# MG2639_Cellular_Shield.net
KiCad netlist of a schematic drawn in EAGLE
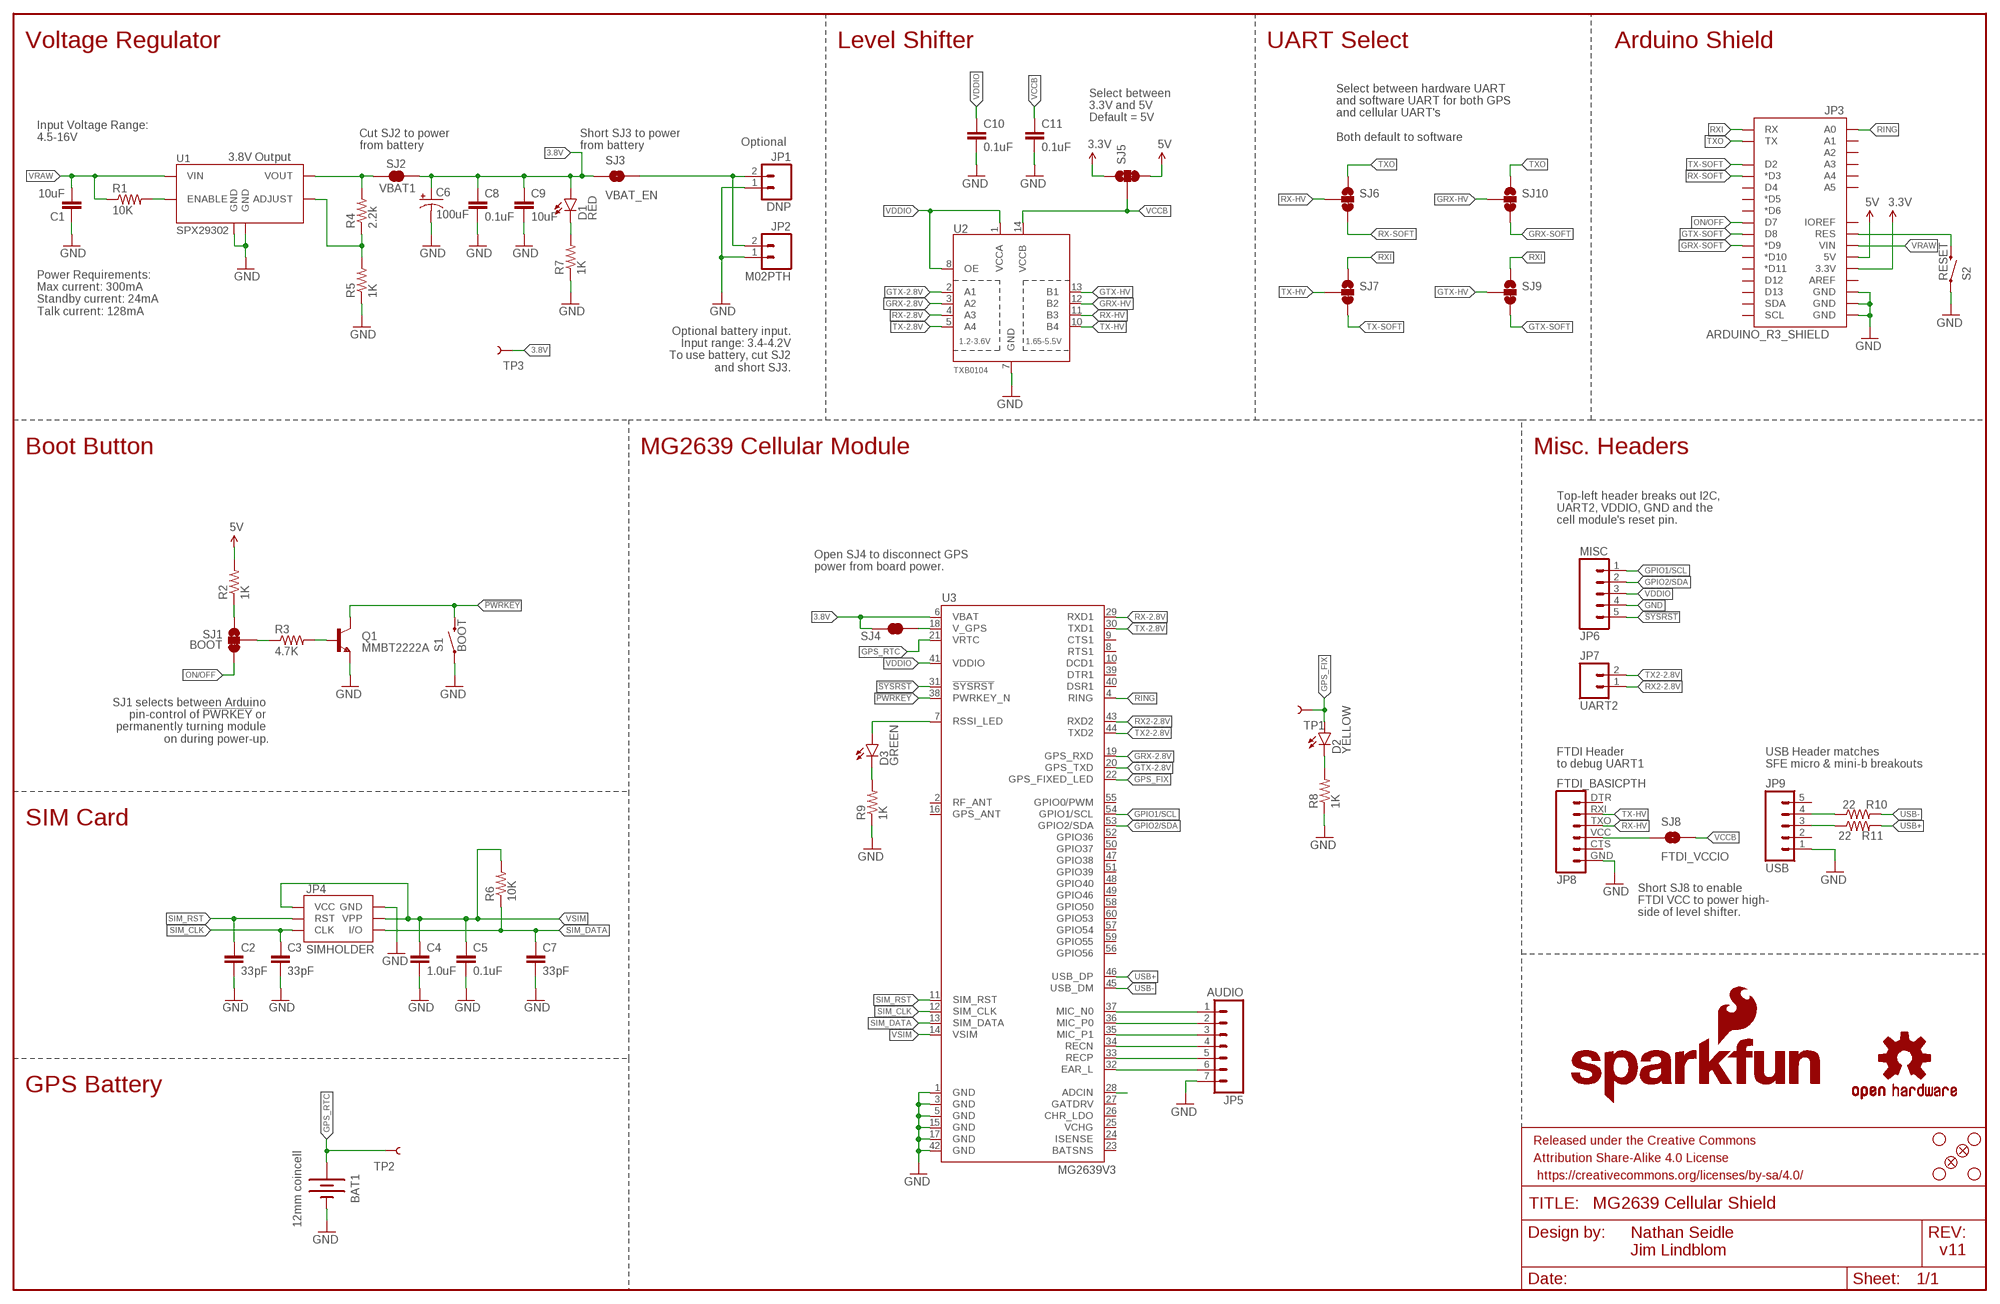
[diagram p0: schematic, sheet 1]

(export (version "E")
  (design (tool "Eeschema 10.0.6"))
  (components
    (comp (ref "BAT1")
      (value "12mm coincell")
      (footprint "eagle-import:BATTCON_12MM")
      (libsource (lib "eagle-import") (part "BATTERY12MM"))
    )
    (comp (ref "C1")
      (value "10uF")
      (footprint "eagle-import:1210")
      (libsource (lib "eagle-import") (part "10UF50V20%(1210)"))
    )
    (comp (ref "C2")
      (value "33pF")
      (footprint "eagle-import:0603-CAP")
      (libsource (lib "eagle-import") (part "33PF-50V-5%-(0603)"))
    )
    (comp (ref "C3")
      (value "33pF")
      (footprint "eagle-import:0603-CAP")
      (libsource (lib "eagle-import") (part "33PF-50V-5%-(0603)"))
    )
    (comp (ref "C4")
      (value "1.0uF")
      (footprint "eagle-import:0603-CAP")
      (libsource (lib "eagle-import") (part "1.0UF-16V-10%(0603)"))
    )
    (comp (ref "C5")
      (value "0.1uF")
      (footprint "eagle-import:0603-CAP")
      (libsource (lib "eagle-import") (part "0.1UF-25V(+80/-20%)(0603)"))
    )
    (comp (ref "C6")
      (value "100uF")
      (footprint "eagle-import:EIA7343")
      (libsource (lib "eagle-import") (part "100UF-10V-10%(TANT)"))
    )
    (comp (ref "C7")
      (value "33pF")
      (footprint "eagle-import:0603-CAP")
      (libsource (lib "eagle-import") (part "33PF-50V-5%-(0603)"))
    )
    (comp (ref "C8")
      (value "0.1uF")
      (footprint "eagle-import:0603-CAP")
      (libsource (lib "eagle-import") (part "0.1UF-25V(+80/-20%)(0603)"))
    )
    (comp (ref "C9")
      (value "10uF")
      (footprint "eagle-import:1210")
      (libsource (lib "eagle-import") (part "10UF50V20%(1210)"))
    )
    (comp (ref "C10")
      (value "0.1uF")
      (footprint "eagle-import:0603-CAP")
      (libsource (lib "eagle-import") (part "0.1UF-25V(+80/-20%)(0603)"))
    )
    (comp (ref "C11")
      (value "0.1uF")
      (footprint "eagle-import:0603-CAP")
      (libsource (lib "eagle-import") (part "0.1UF-25V(+80/-20%)(0603)"))
    )
    (comp (ref "D1")
      (value "RED")
      (footprint "eagle-import:LED-1206")
      (libsource (lib "eagle-import") (part "LED-RED1206"))
    )
    (comp (ref "D2")
      (value "YELLOW")
      (footprint "eagle-import:LED-1206")
      (libsource (lib "eagle-import") (part "LED-YELLOWLARGE"))
    )
    (comp (ref "D3")
      (value "GREEN")
      (footprint "eagle-import:LED-1206")
      (libsource (lib "eagle-import") (part "LED-GREENLARGE"))
    )
    (comp (ref "FID1")
      (value "FIDUCIAL1X2")
      (footprint "eagle-import:FIDUCIAL-1X2")
      (libsource (lib "eagle-import") (part "FIDUCIAL1X2"))
    )
    (comp (ref "FID2")
      (value "FIDUCIAL1X2")
      (footprint "eagle-import:FIDUCIAL-1X2")
      (libsource (lib "eagle-import") (part "FIDUCIAL1X2"))
    )
    (comp (ref "FRAME1")
      (value "FRAME-LEDGER")
      (footprint "eagle-import:CREATIVE_COMMONS")
      (libsource (lib "eagle-import") (part "FRAME-LEDGER"))
    )
    (comp (ref "JP1")
      (value "DNP")
      (footprint "eagle-import:JST-2-PTH")
      (libsource (lib "eagle-import") (part "M02JST-PTH-2"))
    )
    (comp (ref "JP2")
      (value "M02PTH")
      (footprint "eagle-import:1X02")
      (libsource (lib "eagle-import") (part "M02PTH"))
    )
    (comp (ref "JP3")
      (value "ARDUINO_R3_SHIELD")
      (footprint "eagle-import:UNO_R3_SHIELD_NOLABELS")
      (libsource (lib "eagle-import") (part "ARDUINO_R3_SHIELDNOLABELS"))
    )
    (comp (ref "JP4")
      (value "SIMHOLDER")
      (footprint "eagle-import:SIMHOLDER")
      (libsource (lib "eagle-import") (part "SIMHOLDERSIM"))
    )
    (comp (ref "JP5")
      (value "AUDIO")
      (footprint "eagle-import:1X07")
      (libsource (lib "eagle-import") (part "M07"))
    )
    (comp (ref "JP6")
      (value "MISC")
      (footprint "eagle-import:1X05")
      (libsource (lib "eagle-import") (part "M05PTH"))
    )
    (comp (ref "JP7")
      (value "UART2")
      (footprint "eagle-import:1X02")
      (libsource (lib "eagle-import") (part "M02PTH"))
    )
    (comp (ref "JP8")
      (value "FTDI_BASICPTH")
      (footprint "eagle-import:FTDI_BASIC")
      (libsource (lib "eagle-import") (part "FTDI_BASICPTH"))
    )
    (comp (ref "JP9")
      (value "USB")
      (footprint "eagle-import:1X05")
      (libsource (lib "eagle-import") (part "M05PTH"))
    )
    (comp (ref "LOGO1")
      (value "SFE_LOGO_NAME.1_INCH")
      (footprint "eagle-import:SFE_LOGO_NAME_.1")
      (libsource (lib "eagle-import") (part "SFE_LOGO_NAME.1_INCH"))
    )
    (comp (ref "LOGO2")
      (value "SFE_LOGO_NAME_FLAME.2_INCH")
      (footprint "eagle-import:SFE_LOGO_NAME_FLAME_.2")
      (libsource (lib "eagle-import") (part "SFE_LOGO_NAME_FLAME.2_INCH"))
    )
    (comp (ref "LOGO3")
      (value "OSHW-LOGOS")
      (footprint "eagle-import:OSHW-LOGO-S")
      (libsource (lib "eagle-import") (part "OSHW-LOGOS"))
    )
    (comp (ref "Q1")
      (value "MMBT2222A")
      (footprint "eagle-import:SOT23-3")
      (libsource (lib "eagle-import") (part "TRANSISTOR_NPNMMBT2222A"))
    )
    (comp (ref "R1")
      (value "10K")
      (footprint "eagle-import:0603-RES")
      (libsource (lib "eagle-import") (part "10KOHM1/10W1%(0603)0603"))
    )
    (comp (ref "R2")
      (value "1K")
      (footprint "eagle-import:0603-RES")
      (libsource (lib "eagle-import") (part "1KOHM1/10W1%(0603)"))
    )
    (comp (ref "R3")
      (value "4.7K")
      (footprint "eagle-import:0603")
      (libsource (lib "eagle-import") (part "4.7KOHM1/10W1%(0603)"))
    )
    (comp (ref "R4")
      (value "2.2k")
      (footprint "eagle-import:0603-RES")
      (libsource (lib "eagle-import") (part "2.2KOHM1/10W1%(0603)"))
    )
    (comp (ref "R5")
      (value "1K")
      (footprint "eagle-import:0603-RES")
      (libsource (lib "eagle-import") (part "1KOHM1/10W1%(0603)"))
    )
    (comp (ref "R6")
      (value "10K")
      (footprint "eagle-import:0603-RES")
      (libsource (lib "eagle-import") (part "10KOHM1/10W1%(0603)0603"))
    )
    (comp (ref "R7")
      (value "1K")
      (footprint "eagle-import:0603-RES")
      (libsource (lib "eagle-import") (part "1KOHM1/10W1%(0603)"))
    )
    (comp (ref "R8")
      (value "1K")
      (footprint "eagle-import:0603-RES")
      (libsource (lib "eagle-import") (part "1KOHM1/10W1%(0603)"))
    )
    (comp (ref "R9")
      (value "1K")
      (footprint "eagle-import:0603-RES")
      (libsource (lib "eagle-import") (part "1KOHM1/10W1%(0603)"))
    )
    (comp (ref "R10")
      (value "22")
      (footprint "eagle-import:0603-RES")
      (libsource (lib "eagle-import") (part "22OHM1/10W1%(0603)"))
    )
    (comp (ref "R11")
      (value "22")
      (footprint "eagle-import:0603-RES")
      (libsource (lib "eagle-import") (part "22OHM1/10W1%(0603)"))
    )
    (comp (ref "S1")
      (value "BOOT")
      (footprint "eagle-import:TACTILE-SWITCH-SMD")
      (libsource (lib "eagle-import") (part "SWITCH-MOMENTARY-2SMD"))
    )
    (comp (ref "S2")
      (value "RESET")
      (footprint "eagle-import:TACTILE-SWITCH-SMD")
      (libsource (lib "eagle-import") (part "SWITCH-MOMENTARY-2SMD"))
    )
    (comp (ref "SJ1")
      (value "BOOT")
      (footprint "eagle-import:PAD-JUMPER-3-2OF3_NC_BY_TRACE_YES_SILK_FULL_BOX")
      (libsource (lib "eagle-import") (part "JUMPER-PAD-3-2OF3_NC_BY_TRACE"))
    )
    (comp (ref "SJ2")
      (value "VBAT1")
      (footprint "eagle-import:PAD-JUMPER-2-NC_BY_TRACE_YES_SILK")
      (libsource (lib "eagle-import") (part "JUMPER-PAD-2-NC_BY_TRACE"))
    )
    (comp (ref "SJ3")
      (value "VBAT_EN")
      (footprint "eagle-import:PAD-JUMPER-2-NO_YES_SILK")
      (libsource (lib "eagle-import") (part "JUMPER-PAD-2-NOYES_SILK"))
    )
    (comp (ref "SJ4")
      (value "JUMPER-PAD-2-NC_BY_TRACE")
      (footprint "eagle-import:PAD-JUMPER-2-NC_BY_TRACE_YES_SILK")
      (libsource (lib "eagle-import") (part "JUMPER-PAD-2-NC_BY_TRACE"))
    )
    (comp (ref "SJ5")
      (value "JUMPER-PAD-3-2OF3_NC_BY_TRACE")
      (footprint "eagle-import:PAD-JUMPER-3-2OF3_NC_BY_TRACE_YES_SILK_FULL_BOX")
      (libsource (lib "eagle-import") (part "JUMPER-PAD-3-2OF3_NC_BY_TRACE"))
    )
    (comp (ref "SJ6")
      (value "JUMPER-PAD-3-2OF3_NC_BY_TRACE")
      (footprint "eagle-import:PAD-JUMPER-3-2OF3_NC_BY_TRACE_YES_SILK_FULL_BOX")
      (libsource (lib "eagle-import") (part "JUMPER-PAD-3-2OF3_NC_BY_TRACE"))
    )
    (comp (ref "SJ7")
      (value "JUMPER-PAD-3-2OF3_NC_BY_TRACE")
      (footprint "eagle-import:PAD-JUMPER-3-2OF3_NC_BY_TRACE_YES_SILK_FULL_BOX")
      (libsource (lib "eagle-import") (part "JUMPER-PAD-3-2OF3_NC_BY_TRACE"))
    )
    (comp (ref "SJ8")
      (value "FTDI_VCCIO")
      (footprint "eagle-import:PAD-JUMPER-2-NO_YES_SILK")
      (libsource (lib "eagle-import") (part "JUMPER-PAD-2-NOYES_SILK"))
    )
    (comp (ref "SJ9")
      (value "JUMPER-PAD-3-2OF3_NC_BY_TRACE")
      (footprint "eagle-import:PAD-JUMPER-3-2OF3_NC_BY_TRACE_YES_SILK_FULL_BOX")
      (libsource (lib "eagle-import") (part "JUMPER-PAD-3-2OF3_NC_BY_TRACE"))
    )
    (comp (ref "SJ10")
      (value "JUMPER-PAD-3-2OF3_NC_BY_TRACE")
      (footprint "eagle-import:PAD-JUMPER-3-2OF3_NC_BY_TRACE_YES_SILK_FULL_BOX")
      (libsource (lib "eagle-import") (part "JUMPER-PAD-3-2OF3_NC_BY_TRACE"))
    )
    (comp (ref "STANDOFF1")
      (value "STAND-OFF")
      (footprint "eagle-import:STAND-OFF")
      (libsource (lib "eagle-import") (part "STAND-OFF"))
    )
    (comp (ref "STANDOFF2")
      (value "STAND-OFF")
      (footprint "eagle-import:STAND-OFF")
      (libsource (lib "eagle-import") (part "STAND-OFF"))
    )
    (comp (ref "STANDOFF3")
      (value "STAND-OFF")
      (footprint "eagle-import:STAND-OFF")
      (libsource (lib "eagle-import") (part "STAND-OFF"))
    )
    (comp (ref "STANDOFF4")
      (value "STAND-OFF")
      (footprint "eagle-import:STAND-OFF")
      (libsource (lib "eagle-import") (part "STAND-OFF"))
    )
    (comp (ref "TP1")
      (value "TEST-POINT3X5")
      (footprint "eagle-import:PAD.03X.05")
      (libsource (lib "eagle-import") (part "TEST-POINT3X5"))
    )
    (comp (ref "TP2")
      (value "TEST-POINT3X5")
      (footprint "eagle-import:PAD.03X.05")
      (libsource (lib "eagle-import") (part "TEST-POINT3X5"))
    )
    (comp (ref "TP3")
      (value "TEST-POINT3X5")
      (footprint "eagle-import:PAD.03X.05")
      (libsource (lib "eagle-import") (part "TEST-POINT3X5"))
    )
    (comp (ref "U1")
      (value "SPX29302")
      (footprint "eagle-import:Q5-DD_SPX29300")
      (libsource (lib "eagle-import") (part "SPX29302"))
    )
    (comp (ref "U2")
      (value "TXB0104")
      (footprint "eagle-import:SO14")
      (libsource (lib "eagle-import") (part "TXB0104PWRSOIC14"))
    )
    (comp (ref "U3")
      (value "MG2639V3")
      (footprint "eagle-import:MG2639")
      (libsource (lib "eagle-import") (part "MG2639V3"))
    )
  )
  (nets
    (net (code "1") (name "/VCHG") (class "Default")
      (node (ref "U3") (pin "25") (pinfunction "VCHG_25") (pintype "power_in"))
    )
    (net (code "2") (name "/~{PWRKEY}") (class "Default")
      (node (ref "Q1") (pin "3") (pinfunction "C_3") (pintype "passive"))
      (node (ref "S1") (pin "3") (pinfunction "2_3") (pintype "passive"))
      (node (ref "U3") (pin "38") (pinfunction "PWRKEY_N_38") (pintype "input"))
    )
    (net (code "3") (name "/~{SYSRST}") (class "Default")
      (node (ref "JP6") (pin "5") (pinfunction "5_5") (pintype "passive"))
      (node (ref "U3") (pin "31") (pinfunction "~{SYSRST}_31") (pintype "input"))
    )
    (net (code "4") (name "3.3V") (class "Default")
      (node (ref "JP3") (pin "3.3V") (pinfunction "3.3V_3.3V") (pintype "bidirectional"))
      (node (ref "SJ5") (pin "1") (pinfunction "1_1") (pintype "passive"))
    )
    (net (code "5") (name "3.8V") (class "Default")
      (node (ref "C6") (pin "A") (pinfunction "+_A") (pintype "passive"))
      (node (ref "C8") (pin "1") (pinfunction "1_1") (pintype "passive"))
      (node (ref "C9") (pin "1") (pinfunction "1_1") (pintype "passive"))
      (node (ref "D1") (pin "A") (pinfunction "A_A") (pintype "passive"))
      (node (ref "SJ2") (pin "2") (pinfunction "2_2") (pintype "passive"))
      (node (ref "SJ3") (pin "1") (pinfunction "1_1") (pintype "passive"))
      (node (ref "SJ4") (pin "1") (pinfunction "1_1") (pintype "passive"))
      (node (ref "TP3") (pin "P$1") (pinfunction "1_P$1") (pintype "bidirectional"))
      (node (ref "U3") (pin "6") (pinfunction "VBAT_6") (pintype "power_in"))
    )
    (net (code "6") (name "5V") (class "Default")
      (node (ref "JP3") (pin "5V") (pinfunction "5V_5V") (pintype "bidirectional"))
      (node (ref "R2") (pin "2") (pinfunction "2_2") (pintype "passive"))
      (node (ref "SJ5") (pin "3") (pinfunction "3_3") (pintype "passive"))
    )
    (net (code "7") (name "GND") (class "Default")
      (node (ref "BAT1") (pin "GND") (pinfunction "-_GND") (pintype "power_in"))
      (node (ref "C1") (pin "1") (pinfunction "1_1") (pintype "passive"))
      (node (ref "C10") (pin "2") (pinfunction "2_2") (pintype "passive"))
      (node (ref "C11") (pin "2") (pinfunction "2_2") (pintype "passive"))
      (node (ref "C2") (pin "2") (pinfunction "2_2") (pintype "passive"))
      (node (ref "C3") (pin "2") (pinfunction "2_2") (pintype "passive"))
      (node (ref "C4") (pin "2") (pinfunction "2_2") (pintype "passive"))
      (node (ref "C5") (pin "2") (pinfunction "2_2") (pintype "passive"))
      (node (ref "C6") (pin "C") (pinfunction "-_C") (pintype "passive"))
      (node (ref "C7") (pin "2") (pinfunction "2_2") (pintype "passive"))
      (node (ref "C8") (pin "2") (pinfunction "2_2") (pintype "passive"))
      (node (ref "C9") (pin "2") (pinfunction "2_2") (pintype "passive"))
      (node (ref "JP1") (pin "1") (pinfunction "1_1") (pintype "passive"))
      (node (ref "JP2") (pin "1") (pinfunction "1_1") (pintype "passive"))
      (node (ref "JP3") (pin "GND@0") (pinfunction "GND_GND@0") (pintype "bidirectional"))
      (node (ref "JP3") (pin "GND@1") (pinfunction "GND_GND@1") (pintype "bidirectional"))
      (node (ref "JP3") (pin "GND@2") (pinfunction "GND_GND@2") (pintype "bidirectional"))
      (node (ref "JP4") (pin "C5") (pinfunction "GND_C5") (pintype "power_in"))
      (node (ref "JP5") (pin "7") (pinfunction "7_7") (pintype "passive"))
      (node (ref "JP6") (pin "4") (pinfunction "4_4") (pintype "passive"))
      (node (ref "JP8") (pin "GND") (pinfunction "6_GND") (pintype "passive"))
      (node (ref "JP9") (pin "1") (pinfunction "1_1") (pintype "passive"))
      (node (ref "Q1") (pin "2") (pinfunction "E_2") (pintype "passive"))
      (node (ref "R5") (pin "1") (pinfunction "1_1") (pintype "passive"))
      (node (ref "R7") (pin "1") (pinfunction "1_1") (pintype "passive"))
      (node (ref "R8") (pin "1") (pinfunction "1_1") (pintype "passive"))
      (node (ref "R9") (pin "1") (pinfunction "1_1") (pintype "passive"))
      (node (ref "S1") (pin "1") (pinfunction "1_1") (pintype "passive"))
      (node (ref "S2") (pin "1") (pinfunction "1_1") (pintype "passive"))
      (node (ref "U1") (pin "3") (pinfunction "GND_3") (pintype "bidirectional"))
      (node (ref "U1") (pin "6") (pinfunction "GND_6") (pintype "bidirectional"))
      (node (ref "U2") (pin "7") (pinfunction "GND_7") (pintype "bidirectional"))
      (node (ref "U3") (pin "1") (pinfunction "GND_1") (pintype "power_in"))
      (node (ref "U3") (pin "15") (pinfunction "GND_15") (pintype "power_in"))
      (node (ref "U3") (pin "17") (pinfunction "GND_17") (pintype "power_in"))
      (node (ref "U3") (pin "3") (pinfunction "GND_3") (pintype "power_in"))
      (node (ref "U3") (pin "42") (pinfunction "GND_42") (pintype "power_in"))
      (node (ref "U3") (pin "5") (pinfunction "GND_5") (pintype "power_in"))
    )
    (net (code "8") (name "GPIO1{slash}SCL") (class "Default")
      (node (ref "JP6") (pin "1") (pinfunction "1_1") (pintype "passive"))
      (node (ref "U3") (pin "54") (pinfunction "GPIO1/SCL_54") (pintype "bidirectional"))
    )
    (net (code "9") (name "GPIO2{slash}SDA") (class "Default")
      (node (ref "JP6") (pin "2") (pinfunction "2_2") (pintype "passive"))
      (node (ref "U3") (pin "53") (pinfunction "GPIO2/SDA_53") (pintype "bidirectional"))
    )
    (net (code "10") (name "GPS_FIX") (class "Default")
      (node (ref "D2") (pin "A") (pinfunction "A_A") (pintype "passive"))
      (node (ref "TP1") (pin "P$1") (pinfunction "1_P$1") (pintype "bidirectional"))
      (node (ref "U3") (pin "22") (pinfunction "GPS_FIXED_LED_22") (pintype "output"))
    )
    (net (code "11") (name "GPS_RTC") (class "Default")
      (node (ref "BAT1") (pin "PWR@1") (pinfunction "+_PWR@1") (pintype "power_in"))
      (node (ref "TP2") (pin "P$1") (pinfunction "1_P$1") (pintype "bidirectional"))
      (node (ref "U3") (pin "21") (pinfunction "VRTC_21") (pintype "power_in"))
    )
    (net (code "12") (name "GRX-2.8V") (class "Default")
      (node (ref "U2") (pin "3") (pinfunction "A2_3") (pintype "bidirectional"))
      (node (ref "U3") (pin "19") (pinfunction "GPS_RXD_19") (pintype "input"))
    )
    (net (code "13") (name "GRX-HV") (class "Default")
      (node (ref "SJ10") (pin "2") (pinfunction "2_2") (pintype "passive"))
      (node (ref "U2") (pin "12") (pinfunction "B2_12") (pintype "bidirectional"))
    )
    (net (code "14") (name "GRX-SOFT") (class "Default")
      (node (ref "JP3") (pin "D9") (pinfunction "*D9_D9") (pintype "bidirectional"))
      (node (ref "SJ10") (pin "3") (pinfunction "3_3") (pintype "passive"))
    )
    (net (code "15") (name "GTX-2.8V") (class "Default")
      (node (ref "U2") (pin "2") (pinfunction "A1_2") (pintype "bidirectional"))
      (node (ref "U3") (pin "20") (pinfunction "GPS_TXD_20") (pintype "output"))
    )
    (net (code "16") (name "GTX-HV") (class "Default")
      (node (ref "SJ9") (pin "2") (pinfunction "2_2") (pintype "passive"))
      (node (ref "U2") (pin "13") (pinfunction "B1_13") (pintype "bidirectional"))
    )
    (net (code "17") (name "GTX-SOFT") (class "Default")
      (node (ref "JP3") (pin "D8") (pinfunction "D8_D8") (pintype "bidirectional"))
      (node (ref "SJ9") (pin "3") (pinfunction "3_3") (pintype "passive"))
    )
    (net (code "18") (name "Net-(D1-PadC)") (class "Default")
      (node (ref "D1") (pin "C") (pinfunction "C_C") (pintype "passive"))
      (node (ref "R7") (pin "2") (pinfunction "2_2") (pintype "passive"))
    )
    (net (code "19") (name "Net-(D2-PadC)") (class "Default")
      (node (ref "D2") (pin "C") (pinfunction "C_C") (pintype "passive"))
      (node (ref "R8") (pin "2") (pinfunction "2_2") (pintype "passive"))
    )
    (net (code "20") (name "Net-(D3-PadC)") (class "Default")
      (node (ref "D3") (pin "C") (pinfunction "C_C") (pintype "passive"))
      (node (ref "R9") (pin "2") (pinfunction "2_2") (pintype "passive"))
    )
    (net (code "21") (name "Net-(JP1-Pad2)") (class "Default")
      (node (ref "JP1") (pin "2") (pinfunction "2_2") (pintype "passive"))
      (node (ref "JP2") (pin "2") (pinfunction "2_2") (pintype "passive"))
      (node (ref "SJ3") (pin "2") (pinfunction "2_2") (pintype "passive"))
    )
    (net (code "22") (name "Net-(JP8-4)") (class "Default")
      (node (ref "JP8") (pin "VCC") (pinfunction "4_VCC") (pintype "passive"))
      (node (ref "SJ8") (pin "1") (pinfunction "1_1") (pintype "passive"))
    )
    (net (code "23") (name "Net-(JP9-Pad3)") (class "Default")
      (node (ref "JP9") (pin "3") (pinfunction "3_3") (pintype "passive"))
      (node (ref "R11") (pin "1") (pinfunction "1_1") (pintype "passive"))
    )
    (net (code "24") (name "Net-(JP9-Pad4)") (class "Default")
      (node (ref "JP9") (pin "4") (pinfunction "4_4") (pintype "passive"))
      (node (ref "R10") (pin "1") (pinfunction "1_1") (pintype "passive"))
    )
    (net (code "25") (name "Net-(Q1-B)") (class "Default")
      (node (ref "Q1") (pin "1") (pinfunction "B_1") (pintype "passive"))
      (node (ref "R3") (pin "2") (pinfunction "2_2") (pintype "passive"))
    )
    (net (code "26") (name "Net-(R2-Pad1)") (class "Default")
      (node (ref "R2") (pin "1") (pinfunction "1_1") (pintype "passive"))
      (node (ref "SJ1") (pin "1") (pinfunction "1_1") (pintype "passive"))
    )
    (net (code "27") (name "Net-(R3-Pad1)") (class "Default")
      (node (ref "R3") (pin "1") (pinfunction "1_1") (pintype "passive"))
      (node (ref "SJ1") (pin "2") (pinfunction "2_2") (pintype "passive"))
    )
    (net (code "28") (name "Net-(S2-2)") (class "Default")
      (node (ref "JP3") (pin "RES") (pinfunction "RES_RES") (pintype "bidirectional"))
      (node (ref "S2") (pin "3") (pinfunction "2_3") (pintype "passive"))
    )
    (net (code "29") (name "Net-(U1-ADJUST)") (class "Default")
      (node (ref "R4") (pin "1") (pinfunction "1_1") (pintype "passive"))
      (node (ref "R5") (pin "2") (pinfunction "2_2") (pintype "passive"))
      (node (ref "U1") (pin "5") (pinfunction "ADJUST_5") (pintype "bidirectional"))
    )
    (net (code "30") (name "Net-(U1-ENABLE)") (class "Default")
      (node (ref "R1") (pin "2") (pinfunction "2_2") (pintype "passive"))
      (node (ref "U1") (pin "1") (pinfunction "ENABLE_1") (pintype "bidirectional"))
    )
    (net (code "31") (name "Net-(U1-VOUT)") (class "Default")
      (node (ref "R4") (pin "2") (pinfunction "2_2") (pintype "passive"))
      (node (ref "SJ2") (pin "1") (pinfunction "1_1") (pintype "passive"))
      (node (ref "U1") (pin "4") (pinfunction "VOUT_4") (pintype "bidirectional"))
    )
    (net (code "32") (name "Net-(U3-EAR_L)") (class "Default")
      (node (ref "JP5") (pin "6") (pinfunction "6_6") (pintype "passive"))
      (node (ref "U3") (pin "32") (pinfunction "EAR_L_32") (pintype "output"))
    )
    (net (code "33") (name "Net-(U3-MIC_N0)") (class "Default")
      (node (ref "JP5") (pin "1") (pinfunction "1_1") (pintype "passive"))
      (node (ref "U3") (pin "37") (pinfunction "MIC_N0_37") (pintype "input"))
    )
    (net (code "34") (name "Net-(U3-MIC_P0)") (class "Default")
      (node (ref "JP5") (pin "2") (pinfunction "2_2") (pintype "passive"))
      (node (ref "U3") (pin "36") (pinfunction "MIC_P0_36") (pintype "input"))
    )
    (net (code "35") (name "Net-(U3-MIC_P1)") (class "Default")
      (node (ref "JP5") (pin "3") (pinfunction "3_3") (pintype "passive"))
      (node (ref "U3") (pin "35") (pinfunction "MIC_P1_35") (pintype "input"))
    )
    (net (code "36") (name "Net-(U3-RECN)") (class "Default")
      (node (ref "JP5") (pin "4") (pinfunction "4_4") (pintype "passive"))
      (node (ref "U3") (pin "34") (pinfunction "RECN_34") (pintype "output"))
    )
    (net (code "37") (name "Net-(U3-RECP)") (class "Default")
      (node (ref "JP5") (pin "5") (pinfunction "5_5") (pintype "passive"))
      (node (ref "U3") (pin "33") (pinfunction "RECP_33") (pintype "output"))
    )
    (net (code "38") (name "Net-(U3-RSSI_LED)") (class "Default")
      (node (ref "D3") (pin "A") (pinfunction "A_A") (pintype "passive"))
      (node (ref "U3") (pin "7") (pinfunction "RSSI_LED_7") (pintype "output"))
    )
    (net (code "39") (name "Net-(U3-V_GPS)") (class "Default")
      (node (ref "SJ4") (pin "2") (pinfunction "2_2") (pintype "passive"))
      (node (ref "U3") (pin "18") (pinfunction "V_GPS_18") (pintype "power_in"))
    )
    (net (code "40") (name "ON{slash}OFF") (class "Default")
      (node (ref "JP3") (pin "D7") (pinfunction "D7_D7") (pintype "bidirectional"))
      (node (ref "SJ1") (pin "3") (pinfunction "3_3") (pintype "passive"))
    )
    (net (code "41") (name "RING") (class "Default")
      (node (ref "JP3") (pin "A0") (pinfunction "A0_A0") (pintype "bidirectional"))
      (node (ref "U3") (pin "4") (pinfunction "RING_4") (pintype "output"))
    )
    (net (code "42") (name "RX-2.8V") (class "Default")
      (node (ref "U2") (pin "4") (pinfunction "A3_4") (pintype "bidirectional"))
      (node (ref "U3") (pin "29") (pinfunction "RXD1_29") (pintype "input"))
    )
    (net (code "43") (name "RX-HV") (class "Default")
      (node (ref "JP8") (pin "TXO") (pinfunction "3_TXO") (pintype "passive"))
      (node (ref "SJ6") (pin "2") (pinfunction "2_2") (pintype "passive"))
      (node (ref "U2") (pin "11") (pinfunction "B3_11") (pintype "bidirectional"))
    )
    (net (code "44") (name "RX-SOFT") (class "Default")
      (node (ref "JP3") (pin "D3") (pinfunction "*D3_D3") (pintype "bidirectional"))
      (node (ref "SJ6") (pin "3") (pinfunction "3_3") (pintype "passive"))
    )
    (net (code "45") (name "RX2-2.8V") (class "Default")
      (node (ref "JP7") (pin "1") (pinfunction "1_1") (pintype "passive"))
      (node (ref "U3") (pin "43") (pinfunction "RXD2_43") (pintype "input"))
    )
    (net (code "46") (name "RXI") (class "Default")
      (node (ref "JP3") (pin "RX") (pinfunction "RX_RX") (pintype "bidirectional"))
      (node (ref "SJ7") (pin "1") (pinfunction "1_1") (pintype "passive"))
      (node (ref "SJ9") (pin "1") (pinfunction "1_1") (pintype "passive"))
    )
    (net (code "47") (name "SIM_CLK") (class "Default")
      (node (ref "C3") (pin "1") (pinfunction "1_1") (pintype "passive"))
      (node (ref "JP4") (pin "C3") (pinfunction "CLK_C3") (pintype "input"))
      (node (ref "U3") (pin "12") (pinfunction "SIM_CLK_12") (pintype "output"))
    )
    (net (code "48") (name "SIM_DATA") (class "Default")
      (node (ref "C7") (pin "1") (pinfunction "1_1") (pintype "passive"))
      (node (ref "JP4") (pin "C7") (pinfunction "I/O_C7") (pintype "bidirectional"))
      (node (ref "R6") (pin "1") (pinfunction "1_1") (pintype "passive"))
      (node (ref "U3") (pin "13") (pinfunction "SIM_DATA_13") (pintype "bidirectional"))
    )
    (net (code "49") (name "SIM_RST") (class "Default")
      (node (ref "C2") (pin "1") (pinfunction "1_1") (pintype "passive"))
      (node (ref "JP4") (pin "C2") (pinfunction "RST_C2") (pintype "input"))
      (node (ref "U3") (pin "11") (pinfunction "SIM_RST_11") (pintype "output"))
    )
    (net (code "50") (name "TX-2.8V") (class "Default")
      (node (ref "U2") (pin "5") (pinfunction "A4_5") (pintype "bidirectional"))
      (node (ref "U3") (pin "30") (pinfunction "TXD1_30") (pintype "output"))
    )
    (net (code "51") (name "TX-HV") (class "Default")
      (node (ref "JP8") (pin "RXI") (pinfunction "2_RXI") (pintype "passive"))
      (node (ref "SJ7") (pin "2") (pinfunction "2_2") (pintype "passive"))
      (node (ref "U2") (pin "10") (pinfunction "B4_10") (pintype "bidirectional"))
    )
    (net (code "52") (name "TX-SOFT") (class "Default")
      (node (ref "JP3") (pin "D2") (pinfunction "D2_D2") (pintype "bidirectional"))
      (node (ref "SJ7") (pin "3") (pinfunction "3_3") (pintype "passive"))
    )
    (net (code "53") (name "TX2-2.8V") (class "Default")
      (node (ref "JP7") (pin "2") (pinfunction "2_2") (pintype "passive"))
      (node (ref "U3") (pin "44") (pinfunction "TXD2_44") (pintype "output"))
    )
    (net (code "54") (name "TXO") (class "Default")
      (node (ref "JP3") (pin "TX") (pinfunction "TX_TX") (pintype "bidirectional"))
      (node (ref "SJ10") (pin "1") (pinfunction "1_1") (pintype "passive"))
      (node (ref "SJ6") (pin "1") (pinfunction "1_1") (pintype "passive"))
    )
    (net (code "55") (name "USB+") (class "Default")
      (node (ref "R11") (pin "2") (pinfunction "2_2") (pintype "passive"))
      (node (ref "U3") (pin "46") (pinfunction "USB_DP_46") (pintype "bidirectional"))
    )
    (net (code "56") (name "USB-") (class "Default")
      (node (ref "R10") (pin "2") (pinfunction "2_2") (pintype "passive"))
      (node (ref "U3") (pin "45") (pinfunction "USB_DM_45") (pintype "bidirectional"))
    )
    (net (code "57") (name "VCCB") (class "Default")
      (node (ref "C11") (pin "1") (pinfunction "1_1") (pintype "passive"))
      (node (ref "SJ5") (pin "2") (pinfunction "2_2") (pintype "passive"))
      (node (ref "SJ8") (pin "2") (pinfunction "2_2") (pintype "passive"))
      (node (ref "U2") (pin "14") (pinfunction "VCCB_14") (pintype "bidirectional"))
    )
    (net (code "58") (name "VDDIO") (class "Default")
      (node (ref "C10") (pin "1") (pinfunction "1_1") (pintype "passive"))
      (node (ref "JP6") (pin "3") (pinfunction "3_3") (pintype "passive"))
      (node (ref "U2") (pin "1") (pinfunction "VCCA_1") (pintype "bidirectional"))
      (node (ref "U2") (pin "8") (pinfunction "OE_8") (pintype "bidirectional"))
      (node (ref "U3") (pin "41") (pinfunction "VDDIO_41") (pintype "output"))
    )
    (net (code "59") (name "VRAW") (class "Default")
      (node (ref "C1") (pin "2") (pinfunction "2_2") (pintype "passive"))
      (node (ref "JP3") (pin "VIN") (pinfunction "VIN_VIN") (pintype "bidirectional"))
      (node (ref "R1") (pin "1") (pinfunction "1_1") (pintype "passive"))
      (node (ref "U1") (pin "2") (pinfunction "VIN_2") (pintype "bidirectional"))
    )
    (net (code "60") (name "VSIM") (class "Default")
      (node (ref "C4") (pin "1") (pinfunction "1_1") (pintype "passive"))
      (node (ref "C5") (pin "1") (pinfunction "1_1") (pintype "passive"))
      (node (ref "JP4") (pin "C1") (pinfunction "VCC_C1") (pintype "power_in"))
      (node (ref "JP4") (pin "C6") (pinfunction "VPP_C6") (pintype "input"))
      (node (ref "R6") (pin "2") (pinfunction "2_2") (pintype "passive"))
      (node (ref "U3") (pin "14") (pinfunction "VSIM_14") (pintype "output"))
    )
    (net (code "61") (name "unconnected-(JP3-*D5-PadD5)") (class "Default")
      (node (ref "JP3") (pin "D5") (pinfunction "*D5_D5") (pintype "bidirectional"))
    )
    (net (code "62") (name "unconnected-(JP3-*D6-PadD6)") (class "Default")
      (node (ref "JP3") (pin "D6") (pinfunction "*D6_D6") (pintype "bidirectional"))
    )
    (net (code "63") (name "unconnected-(JP3-*D10-PadD10)") (class "Default")
      (node (ref "JP3") (pin "D10") (pinfunction "*D10_D10") (pintype "bidirectional"))
    )
    (net (code "64") (name "unconnected-(JP3-*D11-PadD11)") (class "Default")
      (node (ref "JP3") (pin "D11") (pinfunction "*D11_D11") (pintype "bidirectional"))
    )
    (net (code "65") (name "unconnected-(JP3-PadA1)") (class "Default")
      (node (ref "JP3") (pin "A1") (pinfunction "A1_A1") (pintype "bidirectional"))
    )
    (net (code "66") (name "unconnected-(JP3-PadA2)") (class "Default")
      (node (ref "JP3") (pin "A2") (pinfunction "A2_A2") (pintype "bidirectional"))
    )
    (net (code "67") (name "unconnected-(JP3-PadA3)") (class "Default")
      (node (ref "JP3") (pin "A3") (pinfunction "A3_A3") (pintype "bidirectional"))
    )
    (net (code "68") (name "unconnected-(JP3-PadA4)") (class "Default")
      (node (ref "JP3") (pin "A4") (pinfunction "A4_A4") (pintype "bidirectional"))
    )
    (net (code "69") (name "unconnected-(JP3-PadA5)") (class "Default")
      (node (ref "JP3") (pin "A5") (pinfunction "A5_A5") (pintype "bidirectional"))
    )
    (net (code "70") (name "unconnected-(JP3-PadAREF)") (class "Default")
      (node (ref "JP3") (pin "AREF") (pinfunction "AREF_AREF") (pintype "bidirectional"))
    )
    (net (code "71") (name "unconnected-(JP3-PadD4)") (class "Default")
      (node (ref "JP3") (pin "D4") (pinfunction "D4_D4") (pintype "bidirectional"))
    )
    (net (code "72") (name "unconnected-(JP3-PadD12)") (class "Default")
      (node (ref "JP3") (pin "D12") (pinfunction "D12_D12") (pintype "bidirectional"))
    )
    (net (code "73") (name "unconnected-(JP3-PadD13)") (class "Default")
      (node (ref "JP3") (pin "D13") (pinfunction "D13_D13") (pintype "bidirectional"))
    )
    (net (code "74") (name "unconnected-(JP3-PadIOREF)") (class "Default")
      (node (ref "JP3") (pin "IOREF") (pinfunction "IOREF_IOREF") (pintype "bidirectional"))
    )
    (net (code "75") (name "unconnected-(JP3-PadSCL)") (class "Default")
      (node (ref "JP3") (pin "SCL") (pinfunction "SCL_SCL") (pintype "bidirectional"))
    )
    (net (code "76") (name "unconnected-(JP3-PadSDA)") (class "Default")
      (node (ref "JP3") (pin "SDA") (pinfunction "SDA_SDA") (pintype "bidirectional"))
    )
    (net (code "77") (name "unconnected-(JP8-1-PadDTR)") (class "Default")
      (node (ref "JP8") (pin "DTR") (pinfunction "1_DTR") (pintype "passive"))
    )
    (net (code "78") (name "unconnected-(JP8-5-PadCTS)") (class "Default")
      (node (ref "JP8") (pin "CTS") (pinfunction "5_CTS") (pintype "passive"))
    )
    (net (code "79") (name "unconnected-(JP9-Pad2)") (class "Default")
      (node (ref "JP9") (pin "2") (pinfunction "2_2") (pintype "passive"))
    )
    (net (code "80") (name "unconnected-(JP9-Pad5)") (class "Default")
      (node (ref "JP9") (pin "5") (pinfunction "5_5") (pintype "passive"))
    )
    (net (code "81") (name "unconnected-(U3-ADCIN-Pad28)") (class "Default")
      (node (ref "U3") (pin "28") (pinfunction "ADCIN_28") (pintype "input"))
    )
    (net (code "82") (name "unconnected-(U3-BATSNS-Pad23)") (class "Default")
      (node (ref "U3") (pin "23") (pinfunction "BATSNS_23") (pintype "input"))
    )
    (net (code "83") (name "unconnected-(U3-CHR_LDO-Pad26)") (class "Default")
      (node (ref "U3") (pin "26") (pinfunction "CHR_LDO_26") (pintype "output"))
    )
    (net (code "84") (name "unconnected-(U3-CTS1-Pad9)") (class "Default")
      (node (ref "U3") (pin "9") (pinfunction "CTS1_9") (pintype "input"))
    )
    (net (code "85") (name "unconnected-(U3-DCD1-Pad10)") (class "Default")
      (node (ref "U3") (pin "10") (pinfunction "DCD1_10") (pintype "output"))
    )
    (net (code "86") (name "unconnected-(U3-DSR1-Pad40)") (class "Default")
      (node (ref "U3") (pin "40") (pinfunction "DSR1_40") (pintype "output"))
    )
    (net (code "87") (name "unconnected-(U3-DTR1-Pad39)") (class "Default")
      (node (ref "U3") (pin "39") (pinfunction "DTR1_39") (pintype "input"))
    )
    (net (code "88") (name "unconnected-(U3-GATDRV-Pad27)") (class "Default")
      (node (ref "U3") (pin "27") (pinfunction "GATDRV_27") (pintype "output"))
    )
    (net (code "89") (name "unconnected-(U3-GPIO0{slash}PWM-Pad55)") (class "Default")
      (node (ref "U3") (pin "55") (pinfunction "GPIO0/PWM_55") (pintype "bidirectional"))
    )
    (net (code "90") (name "unconnected-(U3-GPIO36-Pad52)") (class "Default")
      (node (ref "U3") (pin "52") (pinfunction "GPIO36_52") (pintype "bidirectional"))
    )
    (net (code "91") (name "unconnected-(U3-GPIO37-Pad50)") (class "Default")
      (node (ref "U3") (pin "50") (pinfunction "GPIO37_50") (pintype "bidirectional"))
    )
    (net (code "92") (name "unconnected-(U3-GPIO38-Pad47)") (class "Default")
      (node (ref "U3") (pin "47") (pinfunction "GPIO38_47") (pintype "bidirectional"))
    )
    (net (code "93") (name "unconnected-(U3-GPIO39-Pad51)") (class "Default")
      (node (ref "U3") (pin "51") (pinfunction "GPIO39_51") (pintype "bidirectional"))
    )
    (net (code "94") (name "unconnected-(U3-GPIO40-Pad48)") (class "Default")
      (node (ref "U3") (pin "48") (pinfunction "GPIO40_48") (pintype "bidirectional"))
    )
    (net (code "95") (name "unconnected-(U3-GPIO46-Pad49)") (class "Default")
      (node (ref "U3") (pin "49") (pinfunction "GPIO46_49") (pintype "bidirectional"))
    )
    (net (code "96") (name "unconnected-(U3-GPIO50-Pad58)") (class "Default")
      (node (ref "U3") (pin "58") (pinfunction "GPIO50_58") (pintype "bidirectional"))
    )
    (net (code "97") (name "unconnected-(U3-GPIO53-Pad60)") (class "Default")
      (node (ref "U3") (pin "60") (pinfunction "GPIO53_60") (pintype "bidirectional"))
    )
    (net (code "98") (name "unconnected-(U3-GPIO54-Pad57)") (class "Default")
      (node (ref "U3") (pin "57") (pinfunction "GPIO54_57") (pintype "bidirectional"))
    )
    (net (code "99") (name "unconnected-(U3-GPIO55-Pad59)") (class "Default")
      (node (ref "U3") (pin "59") (pinfunction "GPIO55_59") (pintype "bidirectional"))
    )
    (net (code "100") (name "unconnected-(U3-GPIO56-Pad56)") (class "Default")
      (node (ref "U3") (pin "56") (pinfunction "GPIO56_56") (pintype "bidirectional"))
    )
    (net (code "101") (name "unconnected-(U3-GPS_ANT-Pad16)") (class "Default")
      (node (ref "U3") (pin "16") (pinfunction "GPS_ANT_16") (pintype "input"))
    )
    (net (code "102") (name "unconnected-(U3-ISENSE-Pad24)") (class "Default")
      (node (ref "U3") (pin "24") (pinfunction "ISENSE_24") (pintype "input"))
    )
    (net (code "103") (name "unconnected-(U3-RF_ANT-Pad2)") (class "Default")
      (node (ref "U3") (pin "2") (pinfunction "RF_ANT_2") (pintype "bidirectional"))
    )
    (net (code "104") (name "unconnected-(U3-RTS1-Pad8)") (class "Default")
      (node (ref "U3") (pin "8") (pinfunction "RTS1_8") (pintype "output"))
    )
  )
)
